# battery_case.net
KiCad netlist of a schematic drawn in EAGLE
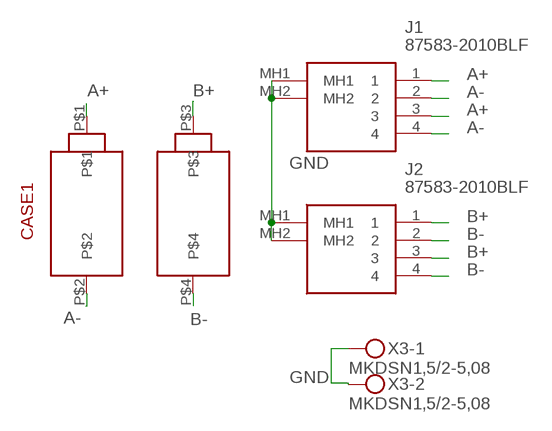
[diagram p0: schematic, sheet 1]

(export (version "E")
  (design (tool "Eeschema 10.0.6"))
  (components
    (comp (ref "CASE1")
      (value "BATTERY_CASE")
      (footprint "eagle-import:CASE")
      (libsource (lib "eagle-import") (part "BATTERY_CASE"))
    )
    (comp (ref "J1")
      (value "87583-2010BLF")
      (footprint "eagle-import:875832010BLF")
      (libsource (lib "eagle-import") (part "87583-2010BLF"))
    )
    (comp (ref "J2")
      (value "87583-2010BLF")
      (footprint "eagle-import:875832010BLF")
      (libsource (lib "eagle-import") (part "87583-2010BLF"))
    )
    (comp (ref "X3")
      (value "MKDSN1,5/2-5,08")
      (footprint "eagle-import:MKDSN1,5_2-5,08")
      (libsource (lib "eagle-import") (part "MKDSN1,5/2-5,08"))
    )
  )
  (nets
    (net (code "1") (name "/A+") (class "Default")
      (node (ref "CASE1") (pin "P$1") (pinfunction "P$1_P$1") (pintype "bidirectional"))
      (node (ref "J1") (pin "1") (pinfunction "1_1") (pintype "bidirectional"))
      (node (ref "J1") (pin "3") (pinfunction "3_3") (pintype "bidirectional"))
    )
    (net (code "2") (name "/A-") (class "Default")
      (node (ref "CASE1") (pin "P$2") (pinfunction "P$2_P$2") (pintype "bidirectional"))
      (node (ref "J1") (pin "2") (pinfunction "2_2") (pintype "bidirectional"))
      (node (ref "J1") (pin "4") (pinfunction "4_4") (pintype "bidirectional"))
    )
    (net (code "3") (name "/B+") (class "Default")
      (node (ref "CASE1") (pin "P$3") (pinfunction "P$3_P$3") (pintype "bidirectional"))
      (node (ref "J2") (pin "1") (pinfunction "1_1") (pintype "bidirectional"))
      (node (ref "J2") (pin "3") (pinfunction "3_3") (pintype "bidirectional"))
    )
    (net (code "4") (name "/B-") (class "Default")
      (node (ref "CASE1") (pin "P$4") (pinfunction "P$4_P$4") (pintype "bidirectional"))
      (node (ref "J2") (pin "2") (pinfunction "2_2") (pintype "bidirectional"))
      (node (ref "J2") (pin "4") (pinfunction "4_4") (pintype "bidirectional"))
    )
    (net (code "5") (name "/GND") (class "Default")
      (node (ref "J1") (pin "MH1") (pinfunction "MH1_MH1") (pintype "bidirectional"))
      (node (ref "J1") (pin "MH2") (pinfunction "MH2_MH2") (pintype "bidirectional"))
      (node (ref "J2") (pin "MH1") (pinfunction "MH1_MH1") (pintype "bidirectional"))
      (node (ref "J2") (pin "MH2") (pinfunction "MH2_MH2") (pintype "bidirectional"))
      (node (ref "X3") (pin "1") (pinfunction "KL_1") (pintype "passive"))
      (node (ref "X3") (pin "2") (pinfunction "KL_2") (pintype "passive"))
    )
  )
)
